# IHM_Schematic.net
KiCad netlist of a schematic drawn in Altium Designer
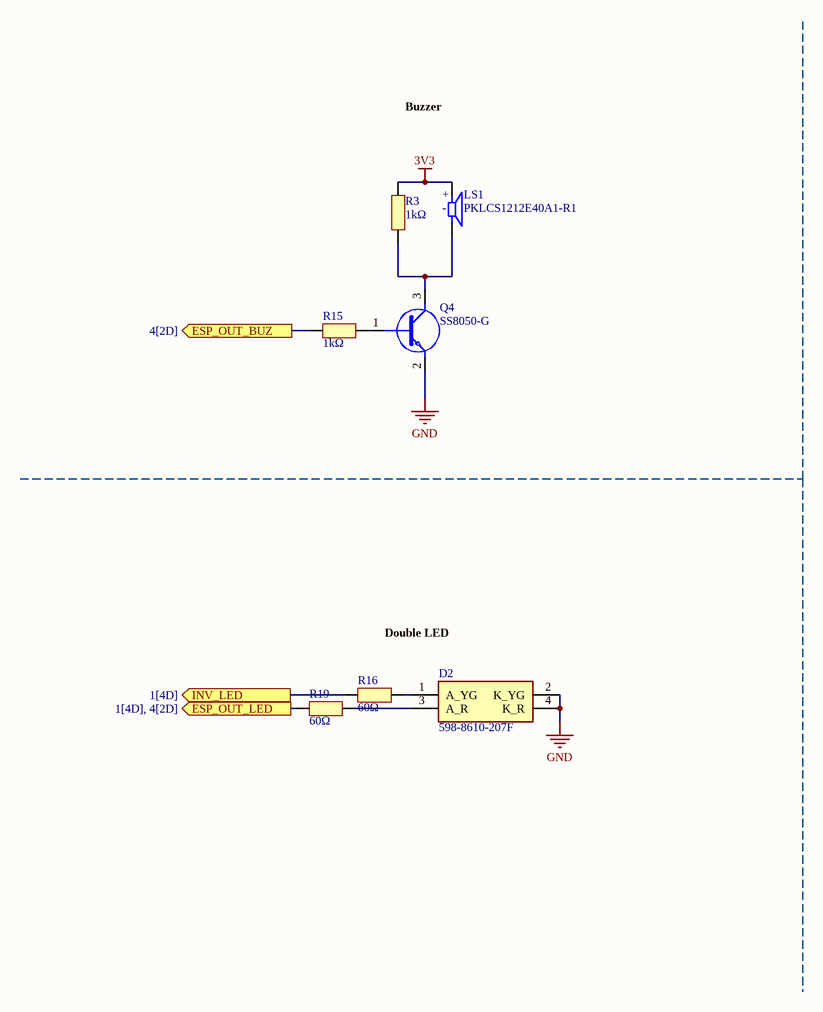
[diagram p0: IHM_Schematic.SchDoc]

(export (version "E")
  (design (tool "Eeschema 10.0.6"))
  (components
    (comp (ref "D2")
      (value "598-8610-207F")
      (footprint "5988610207F")
      (description "Standard LEDs - SMD Red/Green WC 80/50mcd 645/570nm")
      (fields (field (name "MOUSER PART NUMBER") "645-598-8610-207F"))
      (libsource (lib "SCHLibrary") (part "598-8610-207F"))
    )
    (comp (ref "LS1")
      (value "PKLCS1212E40A1-R1")
      (footprint "SPKR_PKLCS1212E40A1-R1")
      (description "Buzzers Transducer, Externally Driven Piezo 1.5V 2kHz 70dB @ 1.5V, 10cm Surface Mount Solder Pads")
      (fields (field (name "MF") "Murata Electronics"))
      (libsource (lib "SCHLibrary") (part "PKLCS1212E40A1-R1"))
    )
    (comp (ref "Q4")
      (value "SS8050-G")
      (footprint "SS8050-G")
      (description "Bipolar Transistors - BJT NPN TRANSISTOR 1.5A 40V")
      (libsource (lib "SCHLibrary") (part "SS8050-G"))
    )
    (comp (ref "R3") (value "1kΩ") (footprint "RESC1005X06N") (libsource (lib "") (part "Resistor_2")))
    (comp (ref "R15")
      (value "1kΩ")
      (footprint "RESC1005X06N")
      (libsource (lib "SCHLibrary") (part "Resistor"))
    )
    (comp (ref "R16") (value "60Ω") (footprint "RESC1005X06N") (libsource (lib "") (part "Resistor_1")))
    (comp (ref "R19")
      (value "60Ω")
      (footprint "RESC1005X06N")
      (libsource (lib "SCHLibrary") (part "Resistor"))
    )
  )
  (nets
    (net (code "1") (name "/ESP_OUT_BUZ") (class "Default")
      (node (ref "R15") (pin "2") (pinfunction "2_2") (pintype "passive"))
    )
    (net (code "2") (name "/ESP_OUT_LED") (class "Default")
      (node (ref "R19") (pin "2") (pinfunction "2_2") (pintype "passive"))
    )
    (net (code "3") (name "/INV_LED") (class "Default")
      (node (ref "R16") (pin "1") (pinfunction "1_1") (pintype "passive"))
    )
    (net (code "4") (name "3V3") (class "Default")
      (node (ref "LS1") (pin "P") (pinfunction "P_P") (pintype "passive"))
      (node (ref "R3") (pin "2") (pinfunction "2_2") (pintype "passive"))
    )
    (net (code "5") (name "GND") (class "Default")
      (node (ref "D2") (pin "2") (pinfunction "K_YG_2") (pintype "passive"))
      (node (ref "D2") (pin "4") (pinfunction "K_R_4") (pintype "passive"))
      (node (ref "Q4") (pin "2") (pinfunction "E_2") (pintype "passive"))
    )
    (net (code "6") (name "Net-(D2-A_R)") (class "Default")
      (node (ref "D2") (pin "3") (pinfunction "A_R_3") (pintype "passive"))
      (node (ref "R19") (pin "1") (pinfunction "1_1") (pintype "passive"))
    )
    (net (code "7") (name "Net-(D2-A_YG)") (class "Default")
      (node (ref "D2") (pin "1") (pinfunction "A_YG_1") (pintype "passive"))
      (node (ref "R16") (pin "2") (pinfunction "2_2") (pintype "passive"))
    )
    (net (code "8") (name "Net-(Q4-B)") (class "Default")
      (node (ref "Q4") (pin "1") (pinfunction "B_1") (pintype "passive"))
      (node (ref "R15") (pin "1") (pinfunction "1_1") (pintype "passive"))
    )
    (net (code "9") (name "Net-(Q4-C)") (class "Default")
      (node (ref "LS1") (pin "N") (pinfunction "N_N") (pintype "passive"))
      (node (ref "Q4") (pin "3") (pinfunction "C_3") (pintype "passive"))
      (node (ref "R3") (pin "1") (pinfunction "1_1") (pintype "passive"))
    )
  )
)
